# XTIDA-010086_MAIN_SHEET.net
KiCad netlist of a schematic drawn in Altium Designer
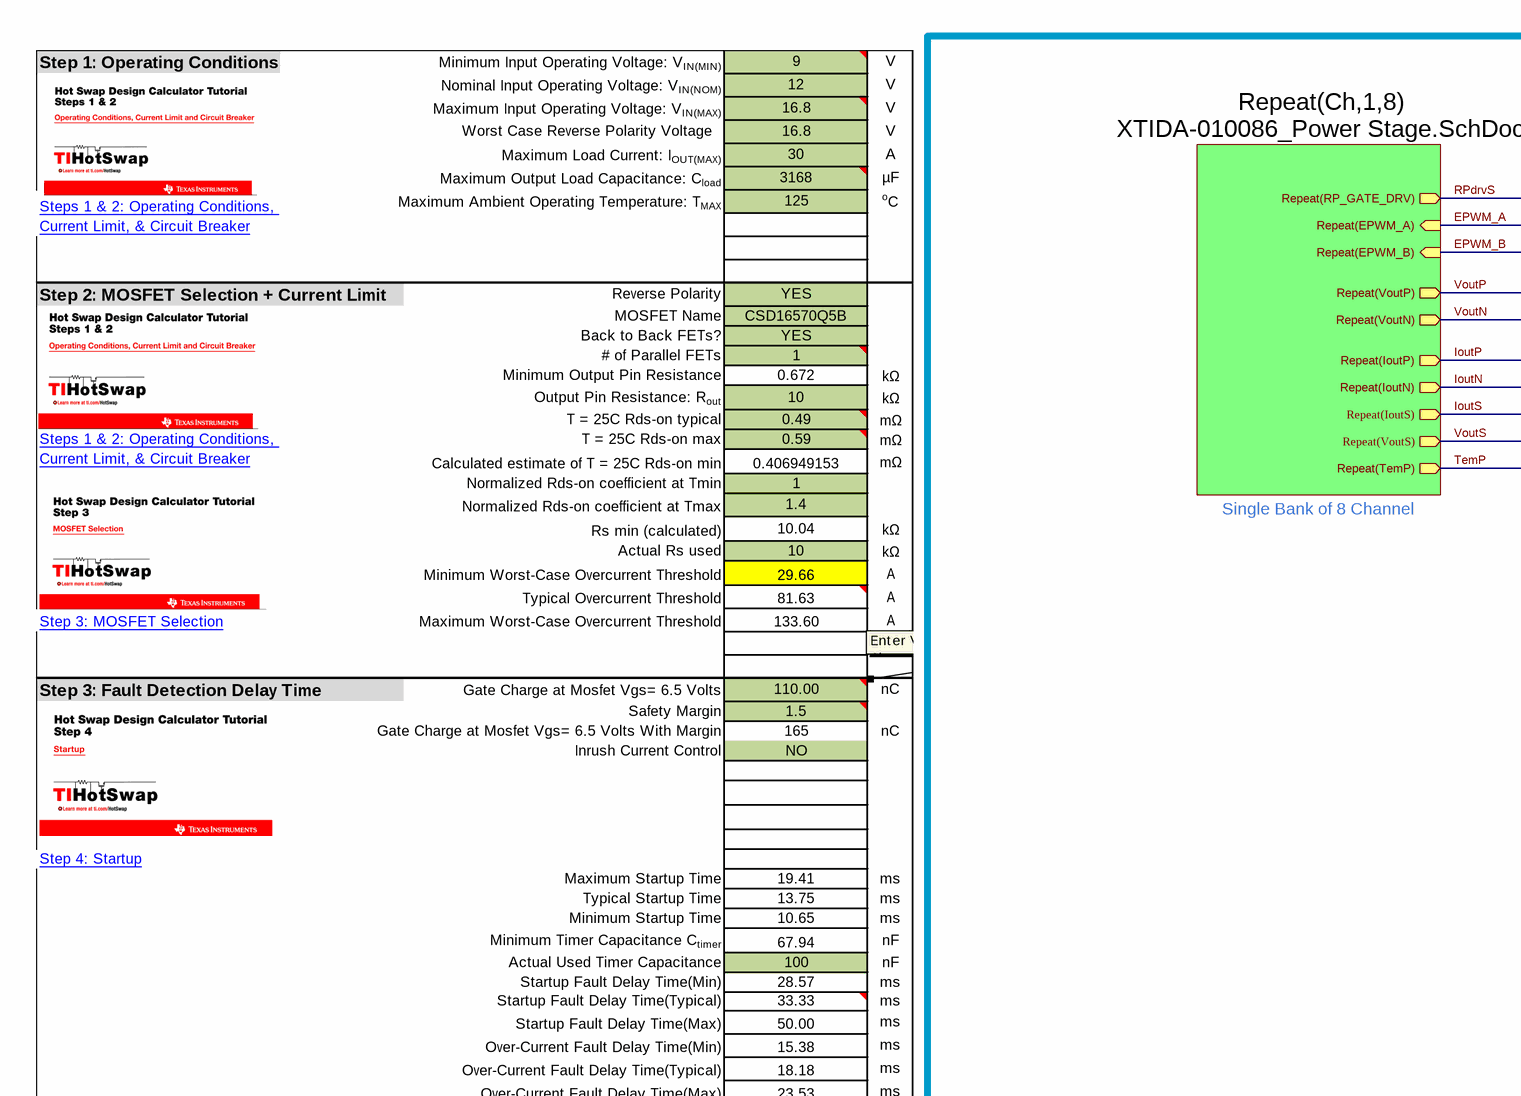
[diagram p0: XTIDA-010086_MAIN SHEET.SchDoc, top left]
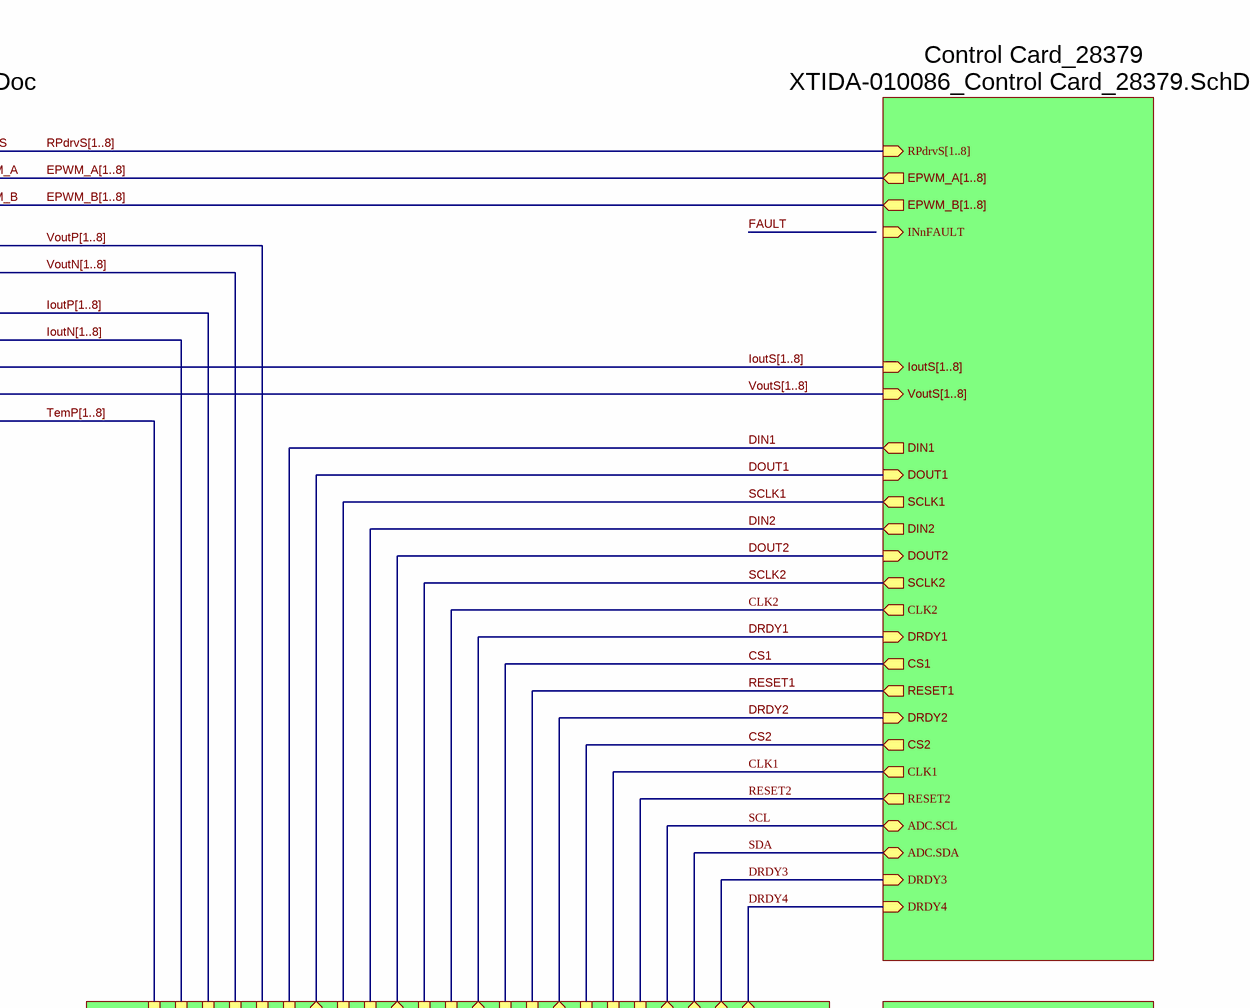
[diagram p1: XTIDA-010086_MAIN SHEET.SchDoc, top right]
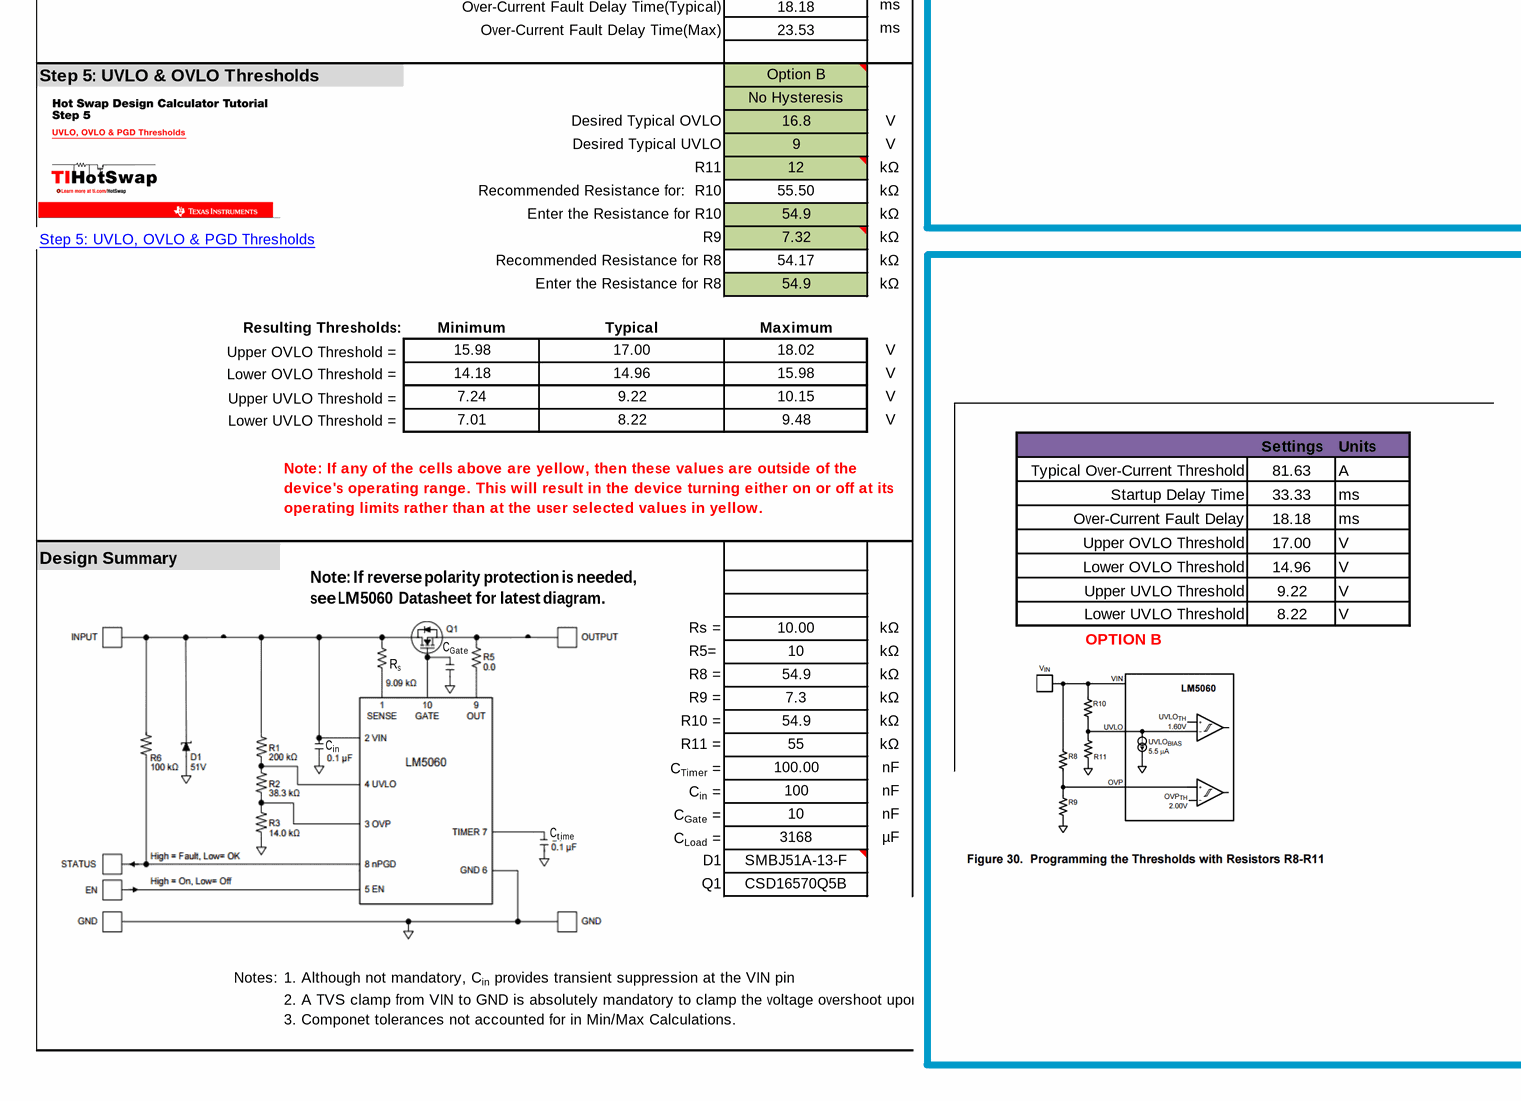
[diagram p2: XTIDA-010086_MAIN SHEET.SchDoc, bottom left]
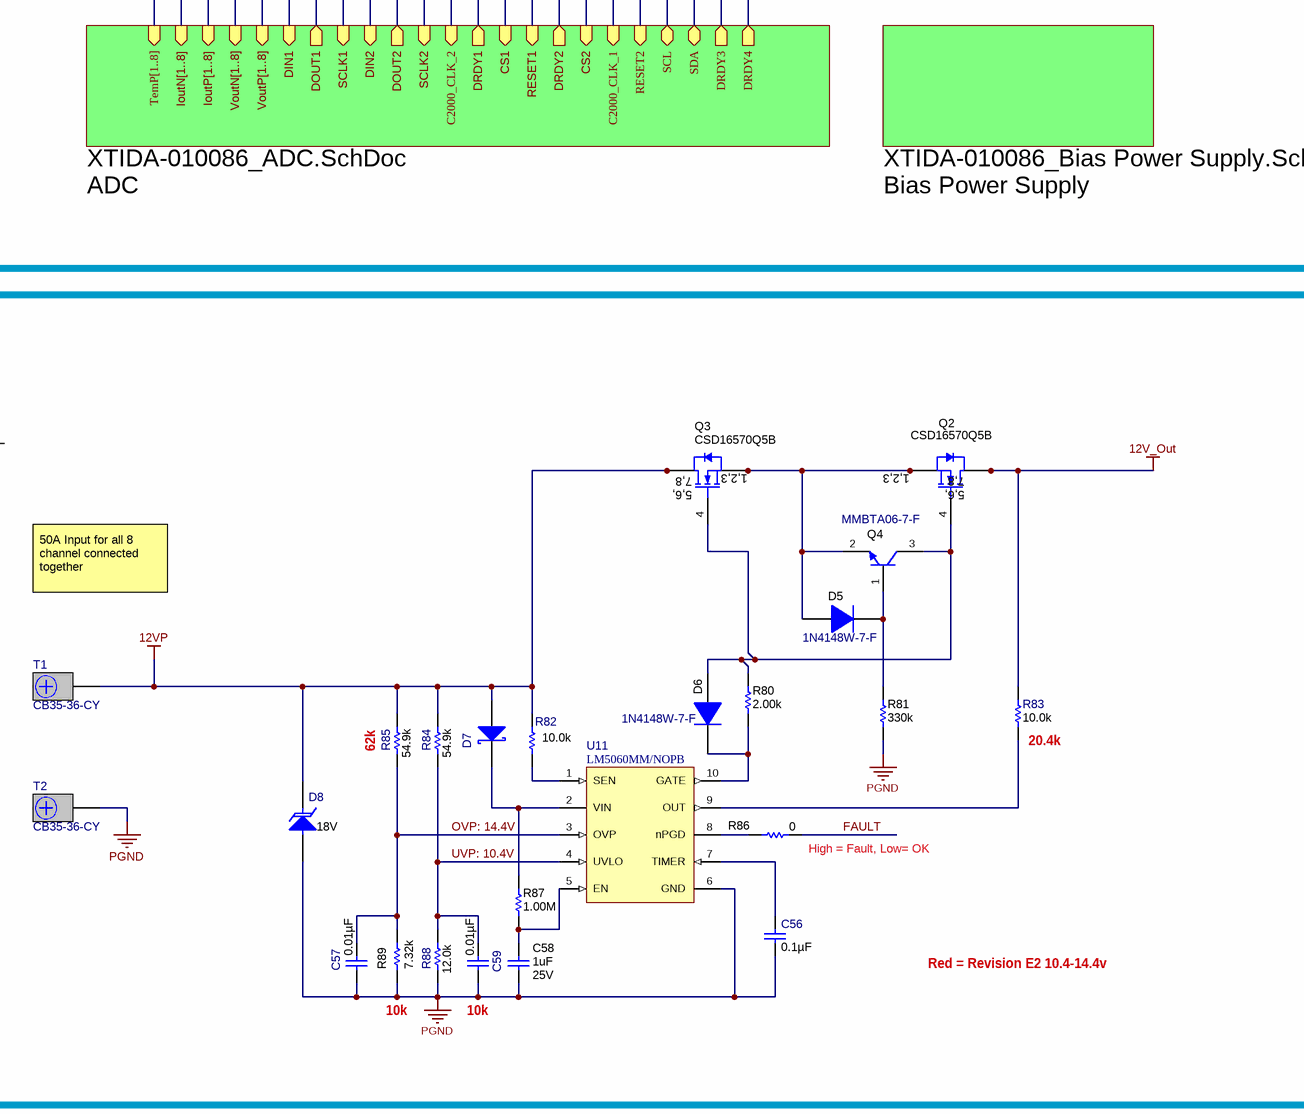
[diagram p3: XTIDA-010086_MAIN SHEET.SchDoc, bottom right]

(export (version "E")
  (design (tool "Eeschema 10.0.6"))
  (components
    (comp (ref "C56")
      (value "C0603C104J3RACTU")
      (footprint "0603L")
      (description "CAP, CERM, 0.1 µF, 25 V, +/- 5%, X7R, 0603")
      (fields
        (field (name "VALUEDISPLAYED") "0.1µF")
        (field (name "MANUFACTURER") "Kemet")
        (field (name "PUBLISHER") "Texas Instruments")
      )
      (libsource (lib "Capacitor_Ceramic") (part "C0603C104J3RACTU"))
    )
    (comp (ref "C57")
      (value "GRM1885C1H103JA01D")
      (footprint "0603L")
      (description "CAP, CERM, 0.01 µF, 50 V, +/- 5%, C0G/NP0, 0603")
      (fields
        (field (name "VALUEDISPLAYED") "0.01µF")
        (field (name "MANUFACTURER") "MuRata")
        (field (name "PUBLISHER") "Texas Instruments")
      )
      (libsource (lib "Capacitor_Ceramic") (part "GRM1885C1H103JA01D"))
    )
    (comp (ref "C58")
      (value "GRM188R71E105KA12D")
      (footprint "0603")
      (description "CAP, CERM, 1 uF, 25 V, +/- 10%, X7R, 0603")
      (fields
        (field (name "VALUEDISPLAYED") "1uF")
        (field (name "MANUFACTURER") "MuRata")
        (field (name "VDC_V") "25V")
        (field (name "PUBLISHER") "Texas Instruments")
      )
      (libsource (lib "Capacitor_Ceramic") (part "Capacitor"))
    )
    (comp (ref "C59")
      (value "GRM1885C1H103JA01D")
      (footprint "0603L")
      (description "CAP, CERM, 0.01 µF, 50 V, +/- 5%, C0G/NP0, 0603")
      (fields
        (field (name "VALUEDISPLAYED") "0.01µF")
        (field (name "MANUFACTURER") "MuRata")
        (field (name "PUBLISHER") "Texas Instruments")
      )
      (libsource (lib "Capacitor_Ceramic") (part "GRM1885C1H103JA01D"))
    )
    (comp (ref "D5")
      (value "1N4148W-7-F")
      (footprint "SOD-123")
      (description "Diode, Ultrafast, 100 V, 0.15 A, SOD-123")
      (fields (field (name "MANUFACTURER") "Diodes Inc.") (field (name "PUBLISHER") "Texas Instruments"))
      (libsource (lib "TIDA-010086") (part "DIODE"))
    )
    (comp (ref "D6")
      (value "1N4148W-7-F")
      (footprint "SOD-123")
      (description "Diode, Ultrafast, 100 V, 0.15 A, SOD-123")
      (fields (field (name "MANUFACTURER") "Diodes Inc.") (field (name "PUBLISHER") "Texas Instruments"))
      (libsource (lib "TIDA-010086") (part "DIODE"))
    )
    (comp (ref "D7")
      (value "NSR0240V2T1G")
      (footprint "SOD-523")
      (description "Diode, Schottky, 40V, 0.25A, SOD-523")
      (fields (field (name "MANUFACTURER") "ON Semiconductor") (field (name "PUBLISHER") "Texas Instruments"))
      (libsource (lib "Diode") (part "NSR0240V2T1G"))
    )
    (comp (ref "D8")
      (value "18V")
      (footprint "SMA")
      (description "Diode, TVS, Uni, 18 V, 29.2 Vc, SMA")
      (fields
        (field (name "PARTNUMBER") "SMAJ18A")
        (field (name "MANUFACTURER") "Littelfuse")
        (field (name "PUBLISHER") "Texas Instruments")
      )
      (libsource (lib "ZenerDiodes") (part "SMAJ18A"))
    )
    (comp (ref "Q2")
      (value "CSD16570Q5B")
      (footprint "DNK0008A")
      (description "MOSFET, N-CH, 25 V, 100 A, DNK0008A (VSON-CLIP-8)")
      (fields
        (field (name "MANUFACTURER") "Texas Instruments")
        (field (name "PUBLISHER") "Texas Instruments")
      )
      (libsource (lib "TIDA-010086") (part "CSD16570Q5B"))
    )
    (comp (ref "Q3")
      (value "CSD16570Q5B")
      (footprint "DNK0008A")
      (description "MOSFET, N-CH, 25 V, 100 A, DNK0008A (VSON-CLIP-8)")
      (fields
        (field (name "MANUFACTURER") "Texas Instruments")
        (field (name "PUBLISHER") "Texas Instruments")
      )
      (libsource (lib "TIDA-010086") (part "CSD16570Q5B"))
    )
    (comp (ref "Q4")
      (value "MMBTA06-7-F")
      (footprint "SOT-23")
      (description "Transistor, NPN, 80 V, 0.5 A, SOT-23")
      (fields (field (name "MANUFACTURER") "Diodes Inc.") (field (name "PUBLISHER") "Texas Instruments"))
      (libsource (lib "TIDA-010086") (part "BJT_NPN_C3B1E2"))
    )
    (comp (ref "R80")
      (value "CRCW06032K00FKEA")
      (footprint "0603")
      (description "RES, 2.00 k, 1%, 0.1 W, 0603")
      (fields
        (field (name "VALUEDISPLAYED") "2.00k")
        (field (name "MANUFACTURER") "Vishay-Dale")
        (field (name "PUBLISHER") "Texas Instruments")
      )
      (libsource (lib "Resistor_0603") (part "CRCW06032K00FKEA"))
    )
    (comp (ref "R81")
      (value "RC0603FR-07330KL")
      (footprint "0603")
      (description "RES, 330 k, 1%, 0.1 W, 0603")
      (fields
        (field (name "VALUEDISPLAYED") "330k")
        (field (name "MANUFACTURER") "Yageo America")
        (field (name "PUBLISHER") "Texas Instruments")
      )
      (libsource (lib "Resistor_0603") (part "RC0603FR-07330KL"))
    )
    (comp (ref "R82")
      (value "RC0603FR-0710KL")
      (footprint "0603L")
      (description "RES, 10.0 k, 1%, 0.1 W, 0603")
      (fields
        (field (name "VALUEDISPLAYED") "10.0k")
        (field (name "MANUFACTURER") "Yageo America")
        (field (name "PUBLISHER") "Texas Instruments")
      )
      (libsource (lib "TIDA-010086") (part "RC0603FR-0710KL"))
    )
    (comp (ref "R83")
      (value "RC0603FR-0710KL")
      (footprint "0603L")
      (description "RES, 10.0 k, 1%, 0.1 W, 0603")
      (fields
        (field (name "VALUEDISPLAYED") "10.0k")
        (field (name "MANUFACTURER") "Yageo America")
        (field (name "PUBLISHER") "Texas Instruments")
      )
      (libsource (lib "TIDA-010086") (part "RC0603FR-0710KL"))
    )
    (comp (ref "R84")
      (value "RC0603FR-0754K9L")
      (footprint "0603L")
      (description "RES, 54.9 k, 1%, 0.1 W, 0603")
      (fields
        (field (name "VALUEDISPLAYED") "54.9k")
        (field (name "MANUFACTURER") "Yageo America")
        (field (name "PUBLISHER") "Texas Instruments")
      )
      (libsource (lib "Resistor_0603") (part "RC0603FR-0754K9L"))
    )
    (comp (ref "R85")
      (value "RC0603FR-0754K9L")
      (footprint "0603L")
      (description "RES, 54.9 k, 1%, 0.1 W, 0603")
      (fields
        (field (name "VALUEDISPLAYED") "54.9k")
        (field (name "MANUFACTURER") "Yageo America")
        (field (name "PUBLISHER") "Texas Instruments")
      )
      (libsource (lib "Resistor_0603") (part "RC0603FR-0754K9L"))
    )
    (comp (ref "R86")
      (value "CRCW04020000Z0ED")
      (footprint "0402")
      (description "RES, 0, 5%, 0.063 W, 0402")
      (fields
        (field (name "VALUEDISPLAYED") "0")
        (field (name "MANUFACTURER") "Vishay-Dale")
        (field (name "PUBLISHER") "Texas Instruments")
      )
      (libsource (lib "Resistor_0402") (part "CRCW04020000Z0ED"))
    )
    (comp (ref "R87")
      (value "CRCW06031M00FKEA")
      (footprint "0603")
      (description "RES, 1.00 M, 1%, 0.1 W, 0603")
      (fields
        (field (name "VALUEDISPLAYED") "1.00M")
        (field (name "MANUFACTURER") "Vishay-Dale")
        (field (name "PUBLISHER") "Texas Instruments")
      )
      (libsource (lib "Resistor_0603") (part "CRCW06031M00FKEA"))
    )
    (comp (ref "R88")
      (value "RC0603FR-0712KL")
      (footprint "0603L")
      (description "RES, 12.0 k, 1%, 0.1 W, 0603")
      (fields
        (field (name "VALUEDISPLAYED") "12.0k")
        (field (name "MANUFACTURER") "Yageo America")
        (field (name "PUBLISHER") "Texas Instruments")
      )
      (libsource (lib "TIDA-010086") (part "RC0603FR-0710KL"))
    )
    (comp (ref "R89")
      (value "RC0603FR-077K32L")
      (footprint "0603L")
      (description "RES, 7.32 k, 1%, 0.1 W, 0603")
      (fields
        (field (name "MANUFACTURER") "Yageo America")
        (field (name "VALUEDISPLAYED") "7.32k")
        (field (name "PUBLISHER") "Texas Instruments")
      )
      (libsource (lib "TIDA-010086") (part "CMP-0023278-3"))
    )
    (comp (ref "T1")
      (value "CB35-36-CY")
      (footprint "CB35-36-CY")
      (description "Terminal 50A Lug")
      (fields
        (field (name "MANUFACTURER") "Panduit")
        (field (name "SYMBOLCREATOR") "crossc")
        (field (name "PUBLISHER") "Texas Instruments")
      )
      (libsource (lib "Connectors_Other") (part "CB35-36-CY"))
    )
    (comp (ref "T2")
      (value "CB35-36-CY")
      (footprint "CB35-36-CY")
      (description "Terminal 50A Lug")
      (fields
        (field (name "MANUFACTURER") "Panduit")
        (field (name "SYMBOLCREATOR") "crossc")
        (field (name "PUBLISHER") "Texas Instruments")
      )
      (libsource (lib "Connectors_Other") (part "CB35-36-CY"))
    )
    (comp (ref "U11")
      (value "LM5060MM/NOPB")
      (footprint "MUB10A_N")
      (description "High-Side Protection Controller with Low Quiescent Current, 10-pin MSOP, Pb-Free")
      (fields (field (name "MANUFACTURER") "Texas Instruments") (field (name "PUBLISHER") "Altium Limited"))
      (libsource (lib "NSC Temperature Sensor") (part "LM5060Q1MMX/NOPB"))
    )
  )
  (nets
    (net (code "97") (name "/FAULT") (class "Default")
      (node (ref "R86") (pin "2") (pinfunction "2_2") (pintype "passive"))
    )
    (net (code "105") (name "/OVP: 14.4V") (class "Default")
      (node (ref "C57") (pin "2") (pinfunction "2_2") (pintype "passive"))
      (node (ref "R85") (pin "1") (pinfunction "1_1") (pintype "passive"))
      (node (ref "R89") (pin "2") (pinfunction "2_2") (pintype "passive"))
      (node (ref "U11") (pin "3") (pinfunction "OVP_3") (pintype "input"))
    )
    (net (code "116") (name "/UVP: 10.4V") (class "Default")
      (node (ref "C59") (pin "2") (pinfunction "2_2") (pintype "passive"))
      (node (ref "R84") (pin "1") (pinfunction "1_1") (pintype "passive"))
      (node (ref "R88") (pin "2") (pinfunction "2_2") (pintype "passive"))
      (node (ref "U11") (pin "4") (pinfunction "UVLO_4") (pintype "input"))
    )
    (net (code "123") (name "12VP") (class "Default")
      (node (ref "D7") (pin "2") (pinfunction "A_2") (pintype "passive"))
      (node (ref "D8") (pin "1") (pinfunction "K_1") (pintype "passive"))
      (node (ref "Q3") (pin "5") (pinfunction "D_5") (pintype "passive"))
      (node (ref "Q3") (pin "6") (pinfunction "D_6") (pintype "passive"))
      (node (ref "Q3") (pin "7") (pinfunction "D_7") (pintype "passive"))
      (node (ref "Q3") (pin "8") (pinfunction "D_8") (pintype "passive"))
      (node (ref "Q3") (pin "9") (pinfunction "D_9") (pintype "passive"))
      (node (ref "R82") (pin "1") (pinfunction "1_1") (pintype "passive"))
      (node (ref "R84") (pin "2") (pinfunction "2_2") (pintype "passive"))
      (node (ref "R85") (pin "2") (pinfunction "2_2") (pintype "passive"))
      (node (ref "T1") (pin "1") (pinfunction "1_1") (pintype "passive"))
    )
    (net (code "124") (name "12V_Out") (class "Default")
      (node (ref "Q2") (pin "5") (pinfunction "D_5") (pintype "passive"))
      (node (ref "Q2") (pin "6") (pinfunction "D_6") (pintype "passive"))
      (node (ref "Q2") (pin "7") (pinfunction "D_7") (pintype "passive"))
      (node (ref "Q2") (pin "8") (pinfunction "D_8") (pintype "passive"))
      (node (ref "Q2") (pin "9") (pinfunction "D_9") (pintype "passive"))
      (node (ref "R83") (pin "2") (pinfunction "2_2") (pintype "passive"))
    )
    (net (code "125") (name "Net-(D5-A)") (class "Default")
      (node (ref "D5") (pin "2") (pinfunction "A_2") (pintype "passive"))
      (node (ref "Q2") (pin "1") (pinfunction "S_1") (pintype "passive"))
      (node (ref "Q2") (pin "2") (pinfunction "S_2") (pintype "passive"))
      (node (ref "Q2") (pin "3") (pinfunction "S_3") (pintype "passive"))
      (node (ref "Q3") (pin "1") (pinfunction "S_1") (pintype "passive"))
      (node (ref "Q3") (pin "2") (pinfunction "S_2") (pintype "passive"))
      (node (ref "Q3") (pin "3") (pinfunction "S_3") (pintype "passive"))
      (node (ref "Q4") (pin "2") (pinfunction "E_2") (pintype "passive"))
    )
    (net (code "126") (name "Net-(D5-K)") (class "Default")
      (node (ref "D5") (pin "1") (pinfunction "K_1") (pintype "passive"))
      (node (ref "Q4") (pin "1") (pinfunction "B_1") (pintype "passive"))
      (node (ref "R81") (pin "2") (pinfunction "2_2") (pintype "passive"))
    )
    (net (code "127") (name "Net-(D6-A)") (class "Default")
      (node (ref "D6") (pin "2") (pinfunction "A_2") (pintype "passive"))
      (node (ref "Q2") (pin "4") (pinfunction "G_4") (pintype "passive"))
      (node (ref "Q3") (pin "4") (pinfunction "G_4") (pintype "passive"))
      (node (ref "Q4") (pin "3") (pinfunction "C_3") (pintype "passive"))
      (node (ref "R80") (pin "2") (pinfunction "2_2") (pintype "passive"))
    )
    (net (code "128") (name "Net-(D6-K)") (class "Default")
      (node (ref "D6") (pin "1") (pinfunction "K_1") (pintype "passive"))
      (node (ref "R80") (pin "1") (pinfunction "1_1") (pintype "passive"))
      (node (ref "U11") (pin "10") (pinfunction "GATE_10") (pintype "output"))
    )
    (net (code "129") (name "Net-(D7-K)") (class "Default")
      (node (ref "D7") (pin "1") (pinfunction "K_1") (pintype "passive"))
      (node (ref "R87") (pin "2") (pinfunction "2_2") (pintype "passive"))
      (node (ref "U11") (pin "2") (pinfunction "VIN_2") (pintype "power_in"))
    )
    (net (code "130") (name "Net-(U11-EN)") (class "Default")
      (node (ref "C58") (pin "1") (pinfunction "1_1") (pintype "passive"))
      (node (ref "R87") (pin "1") (pinfunction "1_1") (pintype "passive"))
      (node (ref "U11") (pin "5") (pinfunction "EN_5") (pintype "input"))
    )
    (net (code "131") (name "Net-(U11-OUT)") (class "Default")
      (node (ref "R83") (pin "1") (pinfunction "1_1") (pintype "passive"))
      (node (ref "U11") (pin "9") (pinfunction "OUT_9") (pintype "output"))
    )
    (net (code "132") (name "Net-(U11-SEN)") (class "Default")
      (node (ref "R82") (pin "2") (pinfunction "2_2") (pintype "passive"))
      (node (ref "U11") (pin "1") (pinfunction "SEN_1") (pintype "input"))
    )
    (net (code "133") (name "Net-(U11-TIMER)") (class "Default")
      (node (ref "C56") (pin "2") (pinfunction "2_2") (pintype "passive"))
      (node (ref "U11") (pin "7") (pinfunction "TIMER_7") (pintype "input"))
    )
    (net (code "134") (name "Net-(U11-nPGD)") (class "Default")
      (node (ref "R86") (pin "1") (pinfunction "1_1") (pintype "passive"))
      (node (ref "U11") (pin "8") (pinfunction "nPGD_8") (pintype "open_collector"))
    )
    (net (code "135") (name "PGND") (class "Default")
      (node (ref "C56") (pin "1") (pinfunction "1_1") (pintype "passive"))
      (node (ref "C57") (pin "1") (pinfunction "1_1") (pintype "passive"))
      (node (ref "C58") (pin "2") (pinfunction "2_2") (pintype "passive"))
      (node (ref "C59") (pin "1") (pinfunction "1_1") (pintype "passive"))
      (node (ref "D8") (pin "2") (pinfunction "A_2") (pintype "passive"))
      (node (ref "R81") (pin "1") (pinfunction "1_1") (pintype "passive"))
      (node (ref "R88") (pin "1") (pinfunction "1_1") (pintype "passive"))
      (node (ref "R89") (pin "1") (pinfunction "1_1") (pintype "passive"))
      (node (ref "T2") (pin "1") (pinfunction "1_1") (pintype "passive"))
      (node (ref "U11") (pin "6") (pinfunction "GND_6") (pintype "power_in"))
    )
  )
)
